# template.net
KiCad netlist of a schematic drawn in EAGLE
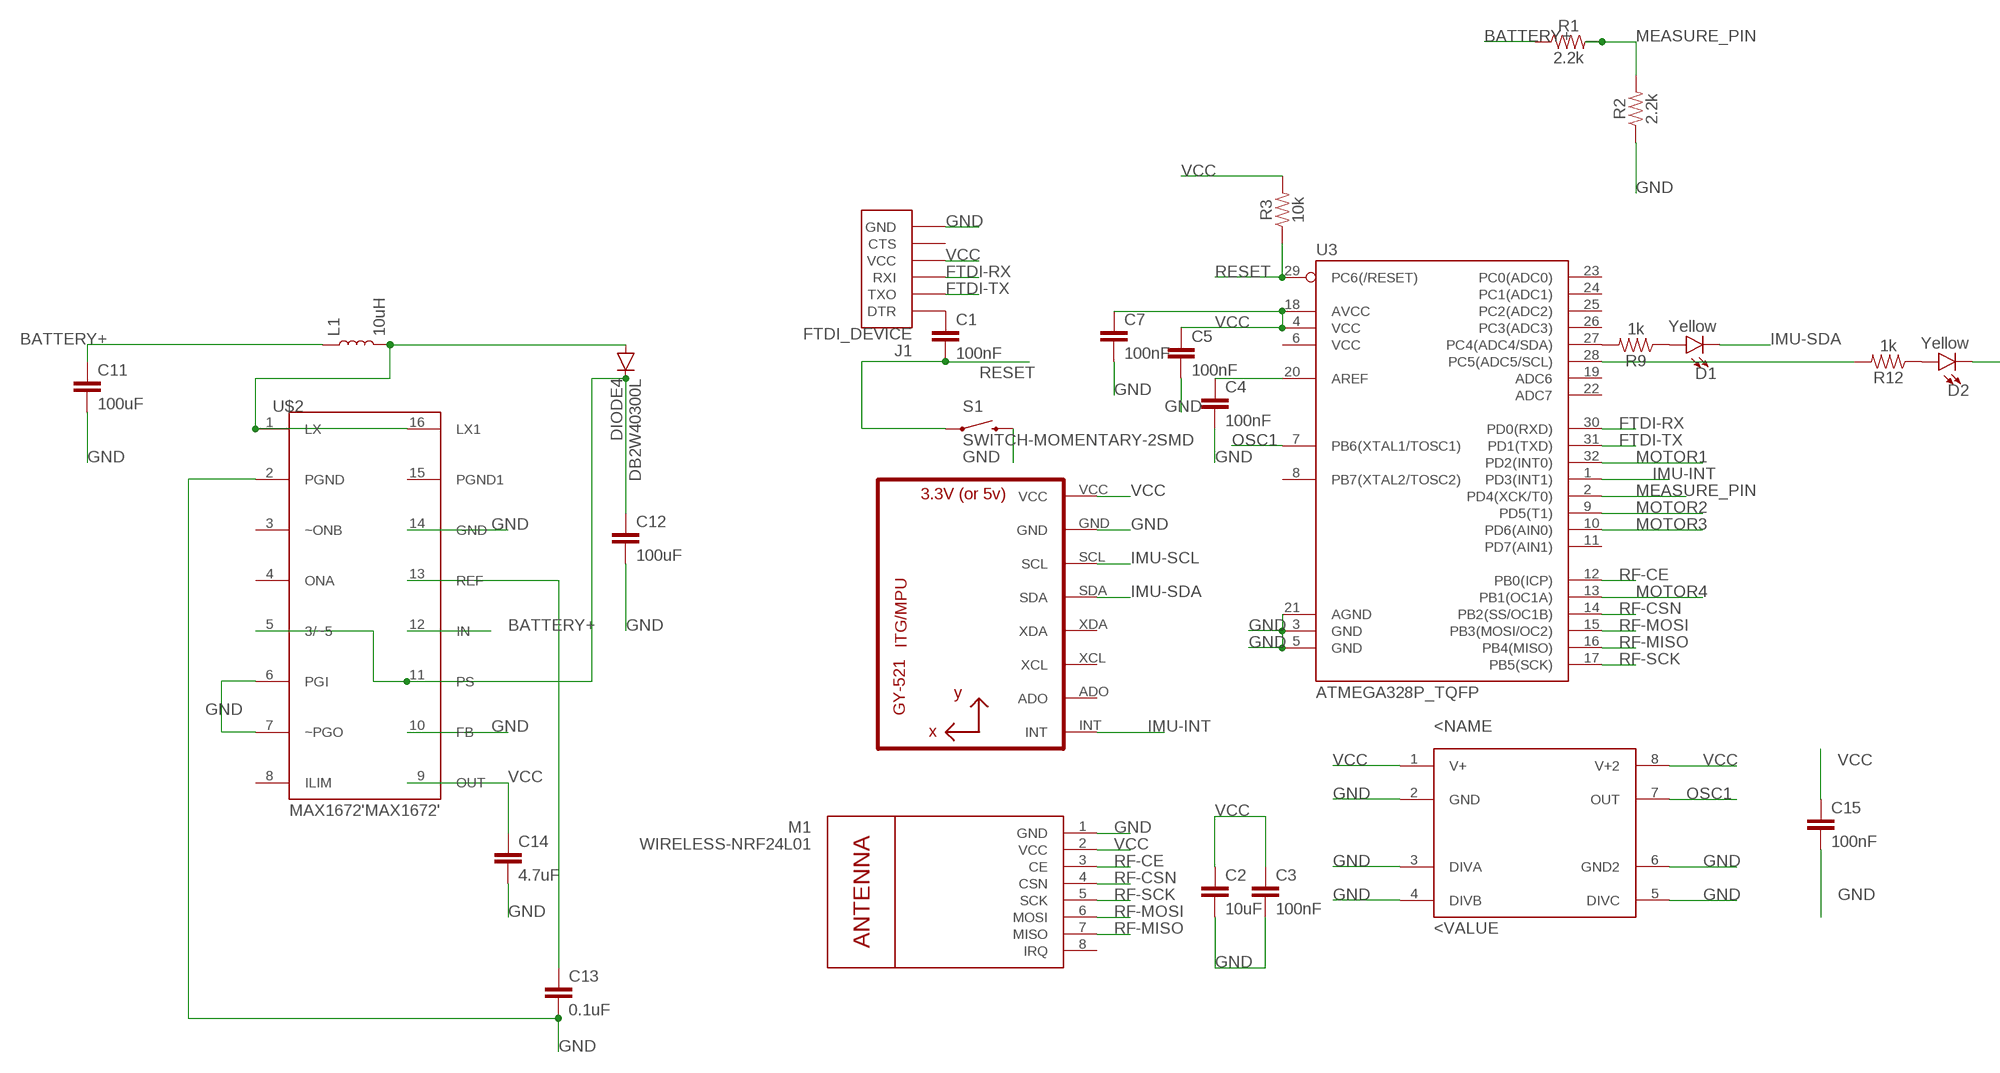
[diagram p0: schematic, sheet 1, part 1 of 2]
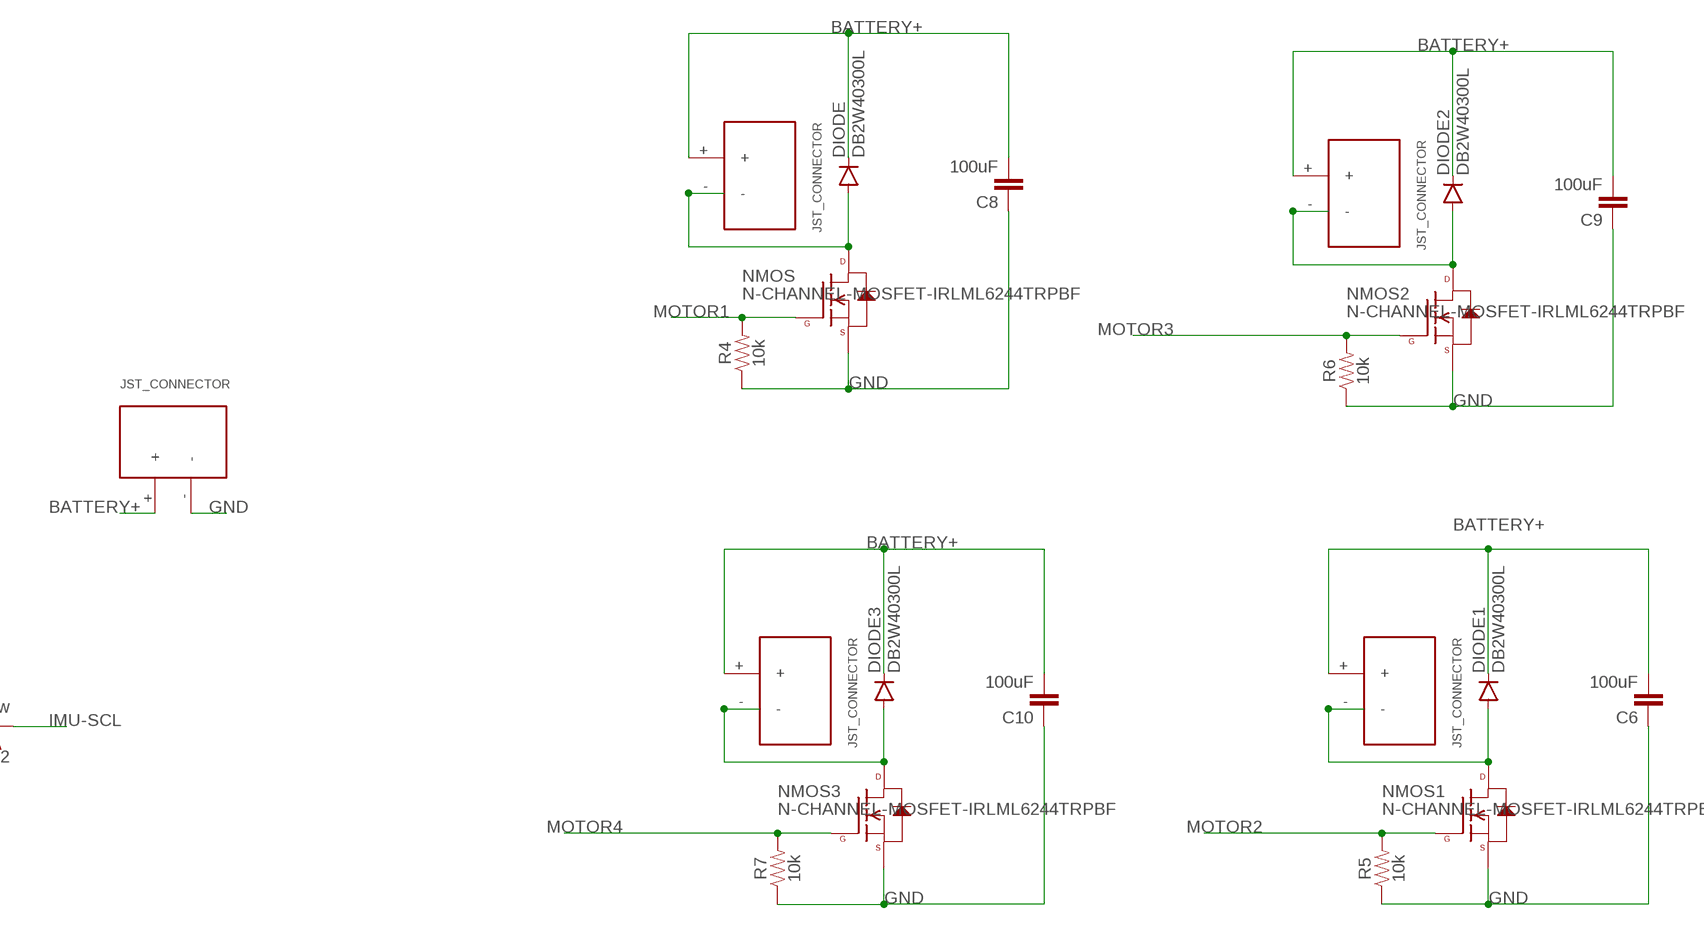
[diagram p1: schematic, sheet 1, part 2 of 2]

(export (version "E")
  (design (tool "Eeschema 10.0.6"))
  (components
    (comp (ref "C1")
      (value "100nF")
      (footprint "eagle-import:0603-CAP")
      (libsource (lib "eagle-import") (part "0.1UF-25V(+80/-20%)(0603)"))
    )
    (comp (ref "C2")
      (value "10uF")
      (footprint "eagle-import:0603-CAP")
      (libsource (lib "eagle-import") (part "CAP0603-CAP"))
    )
    (comp (ref "C3")
      (value "100nF")
      (footprint "eagle-import:0603-CAP")
      (libsource (lib "eagle-import") (part "CAP0603-CAP"))
    )
    (comp (ref "C4")
      (value "100nF")
      (footprint "eagle-import:0603-CAP")
      (libsource (lib "eagle-import") (part "CAP0603-CAP"))
    )
    (comp (ref "C5")
      (value "100nF")
      (footprint "eagle-import:0603-CAP")
      (libsource (lib "eagle-import") (part "CAP0603-CAP"))
    )
    (comp (ref "C6")
      (value "100uF")
      (footprint "eagle-import:0603-CAP")
      (libsource (lib "eagle-import") (part "CAP0603-CAP"))
    )
    (comp (ref "C7")
      (value "100nF")
      (footprint "eagle-import:0603-CAP")
      (libsource (lib "eagle-import") (part "CAP0603-CAP"))
    )
    (comp (ref "C8")
      (value "100uF")
      (footprint "eagle-import:0603-CAP")
      (libsource (lib "eagle-import") (part "CAP0603-CAP"))
    )
    (comp (ref "C9")
      (value "100uF")
      (footprint "eagle-import:0603-CAP")
      (libsource (lib "eagle-import") (part "CAP0603-CAP"))
    )
    (comp (ref "C10")
      (value "100uF")
      (footprint "eagle-import:0603-CAP")
      (libsource (lib "eagle-import") (part "CAP0603-CAP"))
    )
    (comp (ref "C11")
      (value "100uF")
      (footprint "eagle-import:0603-CAP")
      (libsource (lib "eagle-import") (part "CAP0603-CAP"))
    )
    (comp (ref "C12")
      (value "100uF")
      (footprint "eagle-import:0603-CAP")
      (libsource (lib "eagle-import") (part "CAP0603-CAP"))
    )
    (comp (ref "C13")
      (value "0.1uF")
      (footprint "eagle-import:0603-CAP")
      (libsource (lib "eagle-import") (part "CAP0603-CAP"))
    )
    (comp (ref "C14")
      (value "4.7uF")
      (footprint "eagle-import:0603-CAP")
      (libsource (lib "eagle-import") (part "CAP0603-CAP"))
    )
    (comp (ref "C15")
      (value "100nF")
      (footprint "eagle-import:0603-CAP")
      (libsource (lib "eagle-import") (part "0.1UF-25V(+80/-20%)(0603)"))
    )
    (comp (ref "D1")
      (value "Yellow")
      (footprint "eagle-import:LED-1206")
      (libsource (lib "eagle-import") (part "LED-YELLOWLILYPAD"))
    )
    (comp (ref "D2")
      (value "Yellow")
      (footprint "eagle-import:LED-1206")
      (libsource (lib "eagle-import") (part "LED-YELLOWLILYPAD"))
    )
    (comp (ref "DIODE")
      (value "DB2W40300L")
      (footprint "eagle-import:MINI2-F3-B")
      (libsource (lib "eagle-import") (part "DB2W40300L"))
    )
    (comp (ref "DIODE1")
      (value "DB2W40300L")
      (footprint "eagle-import:MINI2-F3-B")
      (libsource (lib "eagle-import") (part "DB2W40300L"))
    )
    (comp (ref "DIODE2")
      (value "DB2W40300L")
      (footprint "eagle-import:MINI2-F3-B")
      (libsource (lib "eagle-import") (part "DB2W40300L"))
    )
    (comp (ref "DIODE3")
      (value "DB2W40300L")
      (footprint "eagle-import:MINI2-F3-B")
      (libsource (lib "eagle-import") (part "DB2W40300L"))
    )
    (comp (ref "DIODE4")
      (value "DB2W40300L")
      (footprint "eagle-import:MINI2-F3-B")
      (libsource (lib "eagle-import") (part "DB2W40300L"))
    )
    (comp (ref "J1")
      (value "FTDI_DEVICE")
      (footprint "eagle-import:FTDI_DEVICE_SIDE")
      (libsource (lib "eagle-import") (part "FTDI_DEVICE"))
    )
    (comp (ref "L1")
      (value "10uH")
      (footprint "eagle-import:0603")
      (libsource (lib "eagle-import") (part "INDUCTOR-0603-33NH"))
    )
    (comp (ref "M1")
      (value "WIRELESS-NRF24L01")
      (footprint "eagle-import:WIRELESS-NRF24L01")
      (libsource (lib "eagle-import") (part "WIRELESS-NRF24L01"))
    )
    (comp (ref "MOTOR1")
      (value "JST_CONNECTOR_FEMALE")
      (footprint "eagle-import:JST_CONNECTOR_FEMALE")
      (libsource (lib "eagle-import") (part "JST_CONNECTOR_FEMALE"))
    )
    (comp (ref "MOTOR2")
      (value "JST_CONNECTOR_FEMALE")
      (footprint "eagle-import:JST_CONNECTOR_FEMALE")
      (libsource (lib "eagle-import") (part "JST_CONNECTOR_FEMALE"))
    )
    (comp (ref "MOTOR3")
      (value "JST_CONNECTOR_FEMALE")
      (footprint "eagle-import:JST_CONNECTOR_FEMALE")
      (libsource (lib "eagle-import") (part "JST_CONNECTOR_FEMALE"))
    )
    (comp (ref "MOTOR4")
      (value "JST_CONNECTOR_FEMALE")
      (footprint "eagle-import:JST_CONNECTOR_FEMALE")
      (libsource (lib "eagle-import") (part "JST_CONNECTOR_FEMALE"))
    )
    (comp (ref "NMOS")
      (value "N-CHANNEL-MOSFET-IRLML6244TRPBF")
      (footprint "eagle-import:SOT23-3")
      (libsource (lib "eagle-import") (part "N-CHANNEL-MOSFET-IRLML6244TRPBF"))
    )
    (comp (ref "NMOS1")
      (value "N-CHANNEL-MOSFET-IRLML6244TRPBF")
      (footprint "eagle-import:SOT23-3")
      (libsource (lib "eagle-import") (part "N-CHANNEL-MOSFET-IRLML6244TRPBF"))
    )
    (comp (ref "NMOS2")
      (value "N-CHANNEL-MOSFET-IRLML6244TRPBF")
      (footprint "eagle-import:SOT23-3")
      (libsource (lib "eagle-import") (part "N-CHANNEL-MOSFET-IRLML6244TRPBF"))
    )
    (comp (ref "NMOS3")
      (value "N-CHANNEL-MOSFET-IRLML6244TRPBF")
      (footprint "eagle-import:SOT23-3")
      (libsource (lib "eagle-import") (part "N-CHANNEL-MOSFET-IRLML6244TRPBF"))
    )
    (comp (ref "R1")
      (value "2.2k")
      (footprint "eagle-import:0603")
      (libsource (lib "eagle-import") (part "2.2KOHM-0603-1/10W-1%"))
    )
    (comp (ref "R2")
      (value "2.2k")
      (footprint "eagle-import:0603")
      (libsource (lib "eagle-import") (part "2.2KOHM-0603-1/10W-1%"))
    )
    (comp (ref "R3")
      (value "10k")
      (footprint "eagle-import:0603")
      (libsource (lib "eagle-import") (part "2.2KOHM-0603-1/10W-1%"))
    )
    (comp (ref "R4")
      (value "10k")
      (footprint "eagle-import:0603")
      (libsource (lib "eagle-import") (part "2.2KOHM-0603-1/10W-1%"))
    )
    (comp (ref "R5")
      (value "10k")
      (footprint "eagle-import:0603")
      (libsource (lib "eagle-import") (part "2.2KOHM-0603-1/10W-1%"))
    )
    (comp (ref "R6")
      (value "10k")
      (footprint "eagle-import:0603")
      (libsource (lib "eagle-import") (part "2.2KOHM-0603-1/10W-1%"))
    )
    (comp (ref "R7")
      (value "10k")
      (footprint "eagle-import:0603")
      (libsource (lib "eagle-import") (part "2.2KOHM-0603-1/10W-1%"))
    )
    (comp (ref "R9")
      (value "1k")
      (footprint "eagle-import:0603")
      (libsource (lib "eagle-import") (part "2.2KOHM-0603-1/10W-1%"))
    )
    (comp (ref "R12")
      (value "1k")
      (footprint "eagle-import:0603")
      (libsource (lib "eagle-import") (part "2.2KOHM-0603-1/10W-1%"))
    )
    (comp (ref "S1")
      (value "SWITCH-MOMENTARY-2SMD")
      (footprint "eagle-import:TACTILE-SWITCH-SMD")
      (libsource (lib "eagle-import") (part "SWITCH-MOMENTARY-2SMD"))
    )
    (comp (ref "U$1")
      (value "JST_CONNECTOR_FEMALE")
      (footprint "eagle-import:JST_CONNECTOR_FEMALE")
      (libsource (lib "eagle-import") (part "JST_CONNECTOR_FEMALE"))
    )
    (comp (ref "U$2")
      (value "MAX1672'MAX1672'")
      (footprint "eagle-import:21-0055H_16")
      (libsource (lib "eagle-import") (part "MAX1672'MAX1672'"))
    )
    (comp (ref "U$3")
      (value "LTC6930CMS8-8.19LTC6930CMS8-8.19")
      (footprint "eagle-import:SOP65P490X110-8N")
      (libsource (lib "eagle-import") (part "LTC6930CMS8-8.19LTC6930CMS8-8.19"))
    )
    (comp (ref "U2")
      (value "GY-521MPU6050")
      (footprint "eagle-import:GY-521")
      (libsource (lib "eagle-import") (part "GY-521MPU6050"))
    )
    (comp (ref "U3")
      (value "ATMEGA328P_TQFP")
      (footprint "eagle-import:TQFP32-08")
      (libsource (lib "eagle-import") (part "ATMEGA328P_TQFP"))
    )
  )
  (nets
    (net (code "1") (name "BATTERY+") (class "Default")
      (node (ref "C10") (pin "2") (pinfunction "2_2") (pintype "passive"))
      (node (ref "C11") (pin "1") (pinfunction "1_1") (pintype "passive"))
      (node (ref "C6") (pin "2") (pinfunction "2_2") (pintype "passive"))
      (node (ref "C8") (pin "2") (pinfunction "2_2") (pintype "passive"))
      (node (ref "C9") (pin "2") (pinfunction "2_2") (pintype "passive"))
      (node (ref "DIODE") (pin "NEG") (pinfunction "GPIN_NEG") (pintype "passive"))
      (node (ref "DIODE1") (pin "NEG") (pinfunction "GPIN_NEG") (pintype "passive"))
      (node (ref "DIODE2") (pin "NEG") (pinfunction "GPIN_NEG") (pintype "passive"))
      (node (ref "DIODE3") (pin "NEG") (pinfunction "GPIN_NEG") (pintype "passive"))
      (node (ref "L1") (pin "1") (pinfunction "1_1") (pintype "passive"))
      (node (ref "MOTOR1") (pin "+") (pinfunction "+_+") (pintype "bidirectional"))
      (node (ref "MOTOR2") (pin "+") (pinfunction "+_+") (pintype "bidirectional"))
      (node (ref "MOTOR3") (pin "+") (pinfunction "+_+") (pintype "bidirectional"))
      (node (ref "MOTOR4") (pin "+") (pinfunction "+_+") (pintype "bidirectional"))
      (node (ref "R1") (pin "1") (pinfunction "1_1") (pintype "passive"))
      (node (ref "U$1") (pin "+") (pinfunction "+_+") (pintype "bidirectional"))
      (node (ref "U$2") (pin "12") (pinfunction "IN_12") (pintype "bidirectional"))
    )
    (net (code "2") (name "FTDI-RX") (class "Default")
      (node (ref "J1") (pin "P$3") (pinfunction "RXI_P$3") (pintype "bidirectional"))
      (node (ref "U3") (pin "30") (pinfunction "PD0(RXD)_30") (pintype "bidirectional"))
    )
    (net (code "3") (name "FTDI-TX") (class "Default")
      (node (ref "J1") (pin "P$2") (pinfunction "TXO_P$2") (pintype "bidirectional"))
      (node (ref "U3") (pin "31") (pinfunction "PD1(TXD)_31") (pintype "bidirectional"))
    )
    (net (code "4") (name "GND") (class "Default")
      (node (ref "C10") (pin "1") (pinfunction "1_1") (pintype "passive"))
      (node (ref "C11") (pin "2") (pinfunction "2_2") (pintype "passive"))
      (node (ref "C12") (pin "2") (pinfunction "2_2") (pintype "passive"))
      (node (ref "C13") (pin "2") (pinfunction "2_2") (pintype "passive"))
      (node (ref "C14") (pin "2") (pinfunction "2_2") (pintype "passive"))
      (node (ref "C15") (pin "2") (pinfunction "2_2") (pintype "passive"))
      (node (ref "C2") (pin "2") (pinfunction "2_2") (pintype "passive"))
      (node (ref "C3") (pin "2") (pinfunction "2_2") (pintype "passive"))
      (node (ref "C4") (pin "2") (pinfunction "2_2") (pintype "passive"))
      (node (ref "C5") (pin "2") (pinfunction "2_2") (pintype "passive"))
      (node (ref "C6") (pin "1") (pinfunction "1_1") (pintype "passive"))
      (node (ref "C7") (pin "2") (pinfunction "2_2") (pintype "passive"))
      (node (ref "C8") (pin "1") (pinfunction "1_1") (pintype "passive"))
      (node (ref "C9") (pin "1") (pinfunction "1_1") (pintype "passive"))
      (node (ref "J1") (pin "P$6") (pinfunction "GND_P$6") (pintype "bidirectional"))
      (node (ref "M1") (pin "1") (pinfunction "GND_1") (pintype "power_in"))
      (node (ref "NMOS") (pin "2") (pinfunction "S_2") (pintype "passive"))
      (node (ref "NMOS1") (pin "2") (pinfunction "S_2") (pintype "passive"))
      (node (ref "NMOS2") (pin "2") (pinfunction "S_2") (pintype "passive"))
      (node (ref "NMOS3") (pin "2") (pinfunction "S_2") (pintype "passive"))
      (node (ref "R2") (pin "1") (pinfunction "1_1") (pintype "passive"))
      (node (ref "R4") (pin "1") (pinfunction "1_1") (pintype "passive"))
      (node (ref "R5") (pin "1") (pinfunction "1_1") (pintype "passive"))
      (node (ref "R6") (pin "1") (pinfunction "1_1") (pintype "passive"))
      (node (ref "R7") (pin "1") (pinfunction "1_1") (pintype "passive"))
      (node (ref "S1") (pin "3") (pinfunction "2_3") (pintype "passive"))
      (node (ref "U$1") (pin "-") (pinfunction "-_-") (pintype "bidirectional"))
      (node (ref "U$2") (pin "10") (pinfunction "FB_10") (pintype "bidirectional"))
      (node (ref "U$2") (pin "14") (pinfunction "GND_14") (pintype "bidirectional"))
      (node (ref "U$2") (pin "2") (pinfunction "PGND_2") (pintype "bidirectional"))
      (node (ref "U$2") (pin "6") (pinfunction "PGI_6") (pintype "bidirectional"))
      (node (ref "U$2") (pin "7") (pinfunction "~{PGO}_7") (pintype "bidirectional"))
      (node (ref "U$3") (pin "2") (pinfunction "GND_2") (pintype "bidirectional"))
      (node (ref "U$3") (pin "3") (pinfunction "DIVA_3") (pintype "bidirectional"))
      (node (ref "U$3") (pin "4") (pinfunction "DIVB_4") (pintype "bidirectional"))
      (node (ref "U$3") (pin "5") (pinfunction "DIVC_5") (pintype "bidirectional"))
      (node (ref "U$3") (pin "6") (pinfunction "GND2_6") (pintype "bidirectional"))
      (node (ref "U2") (pin "GND") (pinfunction "GND_GND") (pintype "bidirectional"))
      (node (ref "U3") (pin "21") (pinfunction "AGND_21") (pintype "bidirectional"))
      (node (ref "U3") (pin "3") (pinfunction "GND_3") (pintype "bidirectional"))
      (node (ref "U3") (pin "5") (pinfunction "GND_5") (pintype "bidirectional"))
    )
    (net (code "5") (name "IMU-INT") (class "Default")
      (node (ref "U2") (pin "INT") (pinfunction "INT_INT") (pintype "bidirectional"))
      (node (ref "U3") (pin "1") (pinfunction "PD3(INT1)_1") (pintype "bidirectional"))
    )
    (net (code "6") (name "IMU-SCL") (class "Default")
      (node (ref "D2") (pin "C") (pinfunction "C_C") (pintype "passive"))
      (node (ref "U2") (pin "SCL") (pinfunction "SCL_SCL") (pintype "bidirectional"))
    )
    (net (code "7") (name "IMU-SDA") (class "Default")
      (node (ref "D1") (pin "C") (pinfunction "C_C") (pintype "passive"))
      (node (ref "U2") (pin "SDA") (pinfunction "SDA_SDA") (pintype "bidirectional"))
    )
    (net (code "8") (name "MEASURE_PIN") (class "Default")
      (node (ref "R1") (pin "2") (pinfunction "2_2") (pintype "passive"))
      (node (ref "R2") (pin "2") (pinfunction "2_2") (pintype "passive"))
      (node (ref "U3") (pin "2") (pinfunction "PD4(XCK/T0)_2") (pintype "bidirectional"))
    )
    (net (code "9") (name "MOTOR1") (class "Default")
      (node (ref "NMOS") (pin "1") (pinfunction "G_1") (pintype "passive"))
      (node (ref "R4") (pin "2") (pinfunction "2_2") (pintype "passive"))
      (node (ref "U3") (pin "32") (pinfunction "PD2(INT0)_32") (pintype "bidirectional"))
    )
    (net (code "10") (name "MOTOR2") (class "Default")
      (node (ref "NMOS1") (pin "1") (pinfunction "G_1") (pintype "passive"))
      (node (ref "R5") (pin "2") (pinfunction "2_2") (pintype "passive"))
      (node (ref "U3") (pin "9") (pinfunction "PD5(T1)_9") (pintype "bidirectional"))
    )
    (net (code "11") (name "MOTOR3") (class "Default")
      (node (ref "NMOS2") (pin "1") (pinfunction "G_1") (pintype "passive"))
      (node (ref "R6") (pin "2") (pinfunction "2_2") (pintype "passive"))
      (node (ref "U3") (pin "10") (pinfunction "PD6(AIN0)_10") (pintype "bidirectional"))
    )
    (net (code "12") (name "MOTOR4") (class "Default")
      (node (ref "NMOS3") (pin "1") (pinfunction "G_1") (pintype "passive"))
      (node (ref "R7") (pin "2") (pinfunction "2_2") (pintype "passive"))
      (node (ref "U3") (pin "13") (pinfunction "PB1(OC1A)_13") (pintype "bidirectional"))
    )
    (net (code "13") (name "Net-(D1-PadA)") (class "Default")
      (node (ref "D1") (pin "A") (pinfunction "A_A") (pintype "passive"))
      (node (ref "R9") (pin "1") (pinfunction "1_1") (pintype "passive"))
    )
    (net (code "14") (name "Net-(D2-PadA)") (class "Default")
      (node (ref "D2") (pin "A") (pinfunction "A_A") (pintype "passive"))
      (node (ref "R12") (pin "1") (pinfunction "1_1") (pintype "passive"))
    )
    (net (code "15") (name "Net-(DIODE-PPIN)") (class "Default")
      (node (ref "DIODE") (pin "POS") (pinfunction "PPIN_POS") (pintype "passive"))
      (node (ref "MOTOR1") (pin "-") (pinfunction "-_-") (pintype "bidirectional"))
      (node (ref "NMOS") (pin "3") (pinfunction "D_3") (pintype "passive"))
    )
    (net (code "16") (name "Net-(DIODE1-PPIN)") (class "Default")
      (node (ref "DIODE1") (pin "POS") (pinfunction "PPIN_POS") (pintype "passive"))
      (node (ref "MOTOR2") (pin "-") (pinfunction "-_-") (pintype "bidirectional"))
      (node (ref "NMOS1") (pin "3") (pinfunction "D_3") (pintype "passive"))
    )
    (net (code "17") (name "Net-(DIODE2-PPIN)") (class "Default")
      (node (ref "DIODE2") (pin "POS") (pinfunction "PPIN_POS") (pintype "passive"))
      (node (ref "MOTOR3") (pin "-") (pinfunction "-_-") (pintype "bidirectional"))
      (node (ref "NMOS2") (pin "3") (pinfunction "D_3") (pintype "passive"))
    )
    (net (code "18") (name "Net-(DIODE3-PPIN)") (class "Default")
      (node (ref "DIODE3") (pin "POS") (pinfunction "PPIN_POS") (pintype "passive"))
      (node (ref "MOTOR4") (pin "-") (pinfunction "-_-") (pintype "bidirectional"))
      (node (ref "NMOS3") (pin "3") (pinfunction "D_3") (pintype "passive"))
    )
    (net (code "19") (name "Net-(DIODE4-GPIN)") (class "Default")
      (node (ref "C12") (pin "1") (pinfunction "1_1") (pintype "passive"))
      (node (ref "DIODE4") (pin "NEG") (pinfunction "GPIN_NEG") (pintype "passive"))
      (node (ref "U$2") (pin "11") (pinfunction "PS_11") (pintype "bidirectional"))
      (node (ref "U$2") (pin "5") (pinfunction "3/~{5}_5") (pintype "bidirectional"))
    )
    (net (code "20") (name "Net-(DIODE4-PPIN)") (class "Default")
      (node (ref "DIODE4") (pin "POS") (pinfunction "PPIN_POS") (pintype "passive"))
      (node (ref "L1") (pin "2") (pinfunction "2_2") (pintype "passive"))
      (node (ref "U$2") (pin "1") (pinfunction "LX_1") (pintype "bidirectional"))
      (node (ref "U$2") (pin "16") (pinfunction "LX1_16") (pintype "bidirectional"))
    )
    (net (code "21") (name "Net-(J1-DTR)") (class "Default")
      (node (ref "C1") (pin "1") (pinfunction "1_1") (pintype "passive"))
      (node (ref "J1") (pin "P$1") (pinfunction "DTR_P$1") (pintype "bidirectional"))
    )
    (net (code "22") (name "Net-(U$2-REF)") (class "Default")
      (node (ref "C13") (pin "1") (pinfunction "1_1") (pintype "passive"))
      (node (ref "U$2") (pin "13") (pinfunction "REF_13") (pintype "bidirectional"))
    )
    (net (code "23") (name "Net-(U3-AREF)") (class "Default")
      (node (ref "C4") (pin "1") (pinfunction "1_1") (pintype "passive"))
      (node (ref "U3") (pin "20") (pinfunction "AREF_20") (pintype "bidirectional"))
    )
    (net (code "24") (name "Net-(U3-PC4(ADC4{slash}SDA))") (class "Default")
      (node (ref "R9") (pin "2") (pinfunction "2_2") (pintype "passive"))
      (node (ref "U3") (pin "27") (pinfunction "PC4(ADC4/SDA)_27") (pintype "bidirectional"))
    )
    (net (code "25") (name "Net-(U3-PC5(ADC5{slash}SCL))") (class "Default")
      (node (ref "R12") (pin "2") (pinfunction "2_2") (pintype "passive"))
      (node (ref "U3") (pin "28") (pinfunction "PC5(ADC5/SCL)_28") (pintype "bidirectional"))
    )
    (net (code "26") (name "OSC1") (class "Default")
      (node (ref "U$3") (pin "7") (pinfunction "OUT_7") (pintype "bidirectional"))
      (node (ref "U3") (pin "7") (pinfunction "PB6(XTAL1/TOSC1)_7") (pintype "bidirectional"))
    )
    (net (code "27") (name "RESET") (class "Default")
      (node (ref "C1") (pin "2") (pinfunction "2_2") (pintype "passive"))
      (node (ref "R3") (pin "1") (pinfunction "1_1") (pintype "passive"))
      (node (ref "S1") (pin "1") (pinfunction "1_1") (pintype "passive"))
      (node (ref "U3") (pin "29") (pinfunction "PC6(/RESET)_29") (pintype "bidirectional"))
    )
    (net (code "28") (name "RF-CE") (class "Default")
      (node (ref "M1") (pin "3") (pinfunction "CE_3") (pintype "bidirectional"))
      (node (ref "U3") (pin "12") (pinfunction "PB0(ICP)_12") (pintype "bidirectional"))
    )
    (net (code "29") (name "RF-CSN") (class "Default")
      (node (ref "M1") (pin "4") (pinfunction "CSN_4") (pintype "bidirectional"))
      (node (ref "U3") (pin "14") (pinfunction "PB2(SS/OC1B)_14") (pintype "bidirectional"))
    )
    (net (code "30") (name "RF-MISO") (class "Default")
      (node (ref "M1") (pin "7") (pinfunction "MISO_7") (pintype "bidirectional"))
      (node (ref "U3") (pin "16") (pinfunction "PB4(MISO)_16") (pintype "bidirectional"))
    )
    (net (code "31") (name "RF-MOSI") (class "Default")
      (node (ref "M1") (pin "6") (pinfunction "MOSI_6") (pintype "bidirectional"))
      (node (ref "U3") (pin "15") (pinfunction "PB3(MOSI/OC2)_15") (pintype "bidirectional"))
    )
    (net (code "32") (name "RF-SCK") (class "Default")
      (node (ref "M1") (pin "5") (pinfunction "SCK_5") (pintype "bidirectional"))
      (node (ref "U3") (pin "17") (pinfunction "PB5(SCK)_17") (pintype "bidirectional"))
    )
    (net (code "33") (name "VCC") (class "Default")
      (node (ref "C14") (pin "1") (pinfunction "1_1") (pintype "passive"))
      (node (ref "C15") (pin "1") (pinfunction "1_1") (pintype "passive"))
      (node (ref "C2") (pin "1") (pinfunction "1_1") (pintype "passive"))
      (node (ref "C3") (pin "1") (pinfunction "1_1") (pintype "passive"))
      (node (ref "C5") (pin "1") (pinfunction "1_1") (pintype "passive"))
      (node (ref "C7") (pin "1") (pinfunction "1_1") (pintype "passive"))
      (node (ref "J1") (pin "P$4") (pinfunction "VCC_P$4") (pintype "bidirectional"))
      (node (ref "M1") (pin "2") (pinfunction "VCC_2") (pintype "power_in"))
      (node (ref "R3") (pin "2") (pinfunction "2_2") (pintype "passive"))
      (node (ref "U$2") (pin "9") (pinfunction "OUT_9") (pintype "bidirectional"))
      (node (ref "U$3") (pin "1") (pinfunction "V+_1") (pintype "bidirectional"))
      (node (ref "U$3") (pin "8") (pinfunction "V+2_8") (pintype "bidirectional"))
      (node (ref "U2") (pin "VCC") (pinfunction "VCC_VCC") (pintype "bidirectional"))
      (node (ref "U3") (pin "18") (pinfunction "AVCC_18") (pintype "bidirectional"))
      (node (ref "U3") (pin "4") (pinfunction "VCC_4") (pintype "bidirectional"))
    )
    (net (code "34") (name "unconnected-(J1-CTS-PadP$5)") (class "Default")
      (node (ref "J1") (pin "P$5") (pinfunction "CTS_P$5") (pintype "bidirectional"))
    )
    (net (code "35") (name "unconnected-(M1-IRQ-Pad8)") (class "Default")
      (node (ref "M1") (pin "8") (pinfunction "IRQ_8") (pintype "bidirectional"))
    )
    (net (code "36") (name "unconnected-(U$2-ILIM-Pad8)") (class "Default")
      (node (ref "U$2") (pin "8") (pinfunction "ILIM_8") (pintype "bidirectional"))
    )
    (net (code "37") (name "unconnected-(U$2-ONA-Pad4)") (class "Default")
      (node (ref "U$2") (pin "4") (pinfunction "ONA_4") (pintype "bidirectional"))
    )
    (net (code "38") (name "unconnected-(U$2-PGND1-Pad15)") (class "Default")
      (node (ref "U$2") (pin "15") (pinfunction "PGND1_15") (pintype "bidirectional"))
    )
    (net (code "39") (name "unconnected-(U$2-~{ONB}-Pad3)") (class "Default")
      (node (ref "U$2") (pin "3") (pinfunction "~{ONB}_3") (pintype "bidirectional"))
    )
    (net (code "40") (name "unconnected-(U2-PadADO)") (class "Default")
      (node (ref "U2") (pin "ADO") (pinfunction "ADO_ADO") (pintype "bidirectional"))
    )
    (net (code "41") (name "unconnected-(U2-PadXCL)") (class "Default")
      (node (ref "U2") (pin "XCL") (pinfunction "XCL_XCL") (pintype "bidirectional"))
    )
    (net (code "42") (name "unconnected-(U2-PadXDA)") (class "Default")
      (node (ref "U2") (pin "XDA") (pinfunction "XDA_XDA") (pintype "bidirectional"))
    )
    (net (code "43") (name "unconnected-(U3-ADC6-Pad19)") (class "Default")
      (node (ref "U3") (pin "19") (pinfunction "ADC6_19") (pintype "bidirectional"))
    )
    (net (code "44") (name "unconnected-(U3-ADC7-Pad22)") (class "Default")
      (node (ref "U3") (pin "22") (pinfunction "ADC7_22") (pintype "bidirectional"))
    )
    (net (code "45") (name "unconnected-(U3-PB7(XTAL2{slash}TOSC2)-Pad8)") (class "Default")
      (node (ref "U3") (pin "8") (pinfunction "PB7(XTAL2/TOSC2)_8") (pintype "bidirectional"))
    )
    (net (code "46") (name "unconnected-(U3-PC0(ADC0)-Pad23)") (class "Default")
      (node (ref "U3") (pin "23") (pinfunction "PC0(ADC0)_23") (pintype "bidirectional"))
    )
    (net (code "47") (name "unconnected-(U3-PC1(ADC1)-Pad24)") (class "Default")
      (node (ref "U3") (pin "24") (pinfunction "PC1(ADC1)_24") (pintype "bidirectional"))
    )
    (net (code "48") (name "unconnected-(U3-PC2(ADC2)-Pad25)") (class "Default")
      (node (ref "U3") (pin "25") (pinfunction "PC2(ADC2)_25") (pintype "bidirectional"))
    )
    (net (code "49") (name "unconnected-(U3-PC3(ADC3)-Pad26)") (class "Default")
      (node (ref "U3") (pin "26") (pinfunction "PC3(ADC3)_26") (pintype "bidirectional"))
    )
    (net (code "50") (name "unconnected-(U3-PD7(AIN1)-Pad11)") (class "Default")
      (node (ref "U3") (pin "11") (pinfunction "PD7(AIN1)_11") (pintype "bidirectional"))
    )
    (net (code "51") (name "unconnected-(U3-VCC-Pad6)") (class "Default")
      (node (ref "U3") (pin "6") (pinfunction "VCC_6") (pintype "bidirectional"))
    )
  )
)
